# uln_0_02.net
KiCad netlist of a schematic drawn in EAGLE
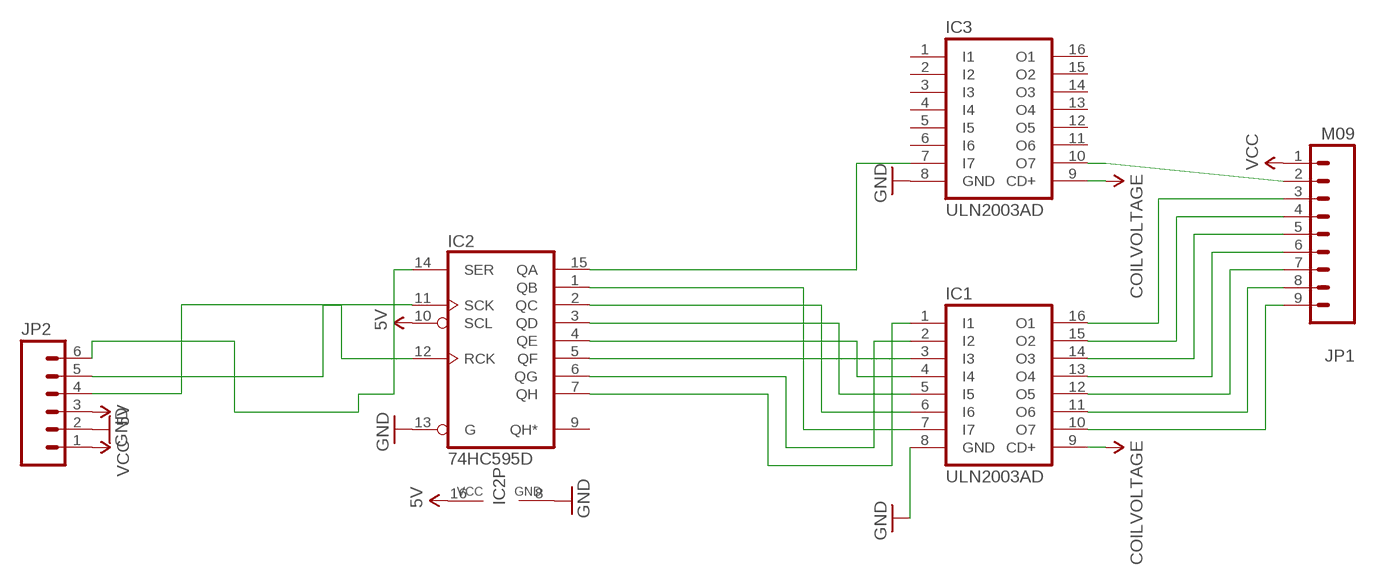
[diagram p0: schematic, sheet 1]

(export (version "E")
  (design (tool "Eeschema 10.0.6"))
  (components
    (comp (ref "IC1")
      (value "ULN2003AD")
      (footprint "eagle-import:SO16")
      (libsource (lib "eagle-import") (part "ULN2003AD"))
    )
    (comp (ref "IC2")
      (value "74HC595D")
      (footprint "eagle-import:SO16")
      (libsource (lib "eagle-import") (part "74595DHC"))
    )
    (comp (ref "IC3")
      (value "ULN2003AD")
      (footprint "eagle-import:SO16")
      (libsource (lib "eagle-import") (part "ULN2003AD"))
    )
    (comp (ref "JP1")
      (value "M09")
      (footprint "eagle-import:1X09")
      (libsource (lib "eagle-import") (part "M09"))
    )
    (comp (ref "JP2")
      (value "M06SIP")
      (footprint "eagle-import:1X06")
      (libsource (lib "eagle-import") (part "M06SIP"))
    )
  )
  (nets
    (net (code "1") (name "5V") (class "Default")
      (node (ref "IC2") (pin "10") (pinfunction "SCL_10") (pintype "input"))
      (node (ref "IC2") (pin "16") (pinfunction "VCC_16") (pintype "power_in"))
      (node (ref "JP2") (pin "3") (pinfunction "3_3") (pintype "passive"))
    )
    (net (code "2") (name "COILVOLTAGE") (class "Default")
      (node (ref "IC1") (pin "9") (pinfunction "CD+_9") (pintype "passive"))
      (node (ref "IC3") (pin "9") (pinfunction "CD+_9") (pintype "passive"))
      (node (ref "JP1") (pin "1") (pinfunction "1_1") (pintype "passive"))
      (node (ref "JP2") (pin "1") (pinfunction "1_1") (pintype "passive"))
    )
    (net (code "3") (name "GND") (class "Default")
      (node (ref "IC1") (pin "8") (pinfunction "GND_8") (pintype "power_in"))
      (node (ref "IC2") (pin "13") (pinfunction "G_13") (pintype "input"))
      (node (ref "IC2") (pin "8") (pinfunction "GND_8") (pintype "power_in"))
      (node (ref "IC3") (pin "8") (pinfunction "GND_8") (pintype "power_in"))
      (node (ref "JP2") (pin "2") (pinfunction "2_2") (pintype "passive"))
    )
    (net (code "4") (name "Net-(IC1-I1)") (class "Default")
      (node (ref "IC1") (pin "1") (pinfunction "I1_1") (pintype "input"))
      (node (ref "IC2") (pin "7") (pinfunction "QH_7") (pintype "tri_state"))
    )
    (net (code "5") (name "Net-(IC1-I2)") (class "Default")
      (node (ref "IC1") (pin "2") (pinfunction "I2_2") (pintype "input"))
      (node (ref "IC2") (pin "6") (pinfunction "QG_6") (pintype "tri_state"))
    )
    (net (code "6") (name "Net-(IC1-I3)") (class "Default")
      (node (ref "IC1") (pin "3") (pinfunction "I3_3") (pintype "input"))
      (node (ref "IC2") (pin "5") (pinfunction "QF_5") (pintype "tri_state"))
    )
    (net (code "7") (name "Net-(IC1-I4)") (class "Default")
      (node (ref "IC1") (pin "4") (pinfunction "I4_4") (pintype "input"))
      (node (ref "IC2") (pin "4") (pinfunction "QE_4") (pintype "tri_state"))
    )
    (net (code "8") (name "Net-(IC1-I5)") (class "Default")
      (node (ref "IC1") (pin "5") (pinfunction "I5_5") (pintype "input"))
      (node (ref "IC2") (pin "3") (pinfunction "QD_3") (pintype "tri_state"))
    )
    (net (code "9") (name "Net-(IC1-I6)") (class "Default")
      (node (ref "IC1") (pin "6") (pinfunction "I6_6") (pintype "input"))
      (node (ref "IC2") (pin "2") (pinfunction "QC_2") (pintype "tri_state"))
    )
    (net (code "10") (name "Net-(IC1-I7)") (class "Default")
      (node (ref "IC1") (pin "7") (pinfunction "I7_7") (pintype "input"))
      (node (ref "IC2") (pin "1") (pinfunction "QB_1") (pintype "tri_state"))
    )
    (net (code "11") (name "Net-(IC1-O1)") (class "Default")
      (node (ref "IC1") (pin "16") (pinfunction "O1_16") (pintype "open_collector"))
      (node (ref "JP1") (pin "3") (pinfunction "3_3") (pintype "passive"))
    )
    (net (code "12") (name "Net-(IC1-O2)") (class "Default")
      (node (ref "IC1") (pin "15") (pinfunction "O2_15") (pintype "open_collector"))
      (node (ref "JP1") (pin "4") (pinfunction "4_4") (pintype "passive"))
    )
    (net (code "13") (name "Net-(IC1-O3)") (class "Default")
      (node (ref "IC1") (pin "14") (pinfunction "O3_14") (pintype "open_collector"))
      (node (ref "JP1") (pin "5") (pinfunction "5_5") (pintype "passive"))
    )
    (net (code "14") (name "Net-(IC1-O4)") (class "Default")
      (node (ref "IC1") (pin "13") (pinfunction "O4_13") (pintype "open_collector"))
      (node (ref "JP1") (pin "6") (pinfunction "6_6") (pintype "passive"))
    )
    (net (code "15") (name "Net-(IC1-O5)") (class "Default")
      (node (ref "IC1") (pin "12") (pinfunction "O5_12") (pintype "open_collector"))
      (node (ref "JP1") (pin "7") (pinfunction "7_7") (pintype "passive"))
    )
    (net (code "16") (name "Net-(IC1-O6)") (class "Default")
      (node (ref "IC1") (pin "11") (pinfunction "O6_11") (pintype "open_collector"))
      (node (ref "JP1") (pin "8") (pinfunction "8_8") (pintype "passive"))
    )
    (net (code "17") (name "Net-(IC1-O7)") (class "Default")
      (node (ref "IC1") (pin "10") (pinfunction "O7_10") (pintype "open_collector"))
      (node (ref "JP1") (pin "9") (pinfunction "9_9") (pintype "passive"))
    )
    (net (code "18") (name "Net-(IC2A-QA)") (class "Default")
      (node (ref "IC2") (pin "15") (pinfunction "QA_15") (pintype "tri_state"))
      (node (ref "IC3") (pin "7") (pinfunction "I7_7") (pintype "input"))
    )
    (net (code "19") (name "Net-(IC2A-RCK)") (class "Default")
      (node (ref "IC2") (pin "12") (pinfunction "RCK_12") (pintype "input"))
      (node (ref "JP2") (pin "5") (pinfunction "5_5") (pintype "passive"))
    )
    (net (code "20") (name "Net-(IC2A-SCK)") (class "Default")
      (node (ref "IC2") (pin "11") (pinfunction "SCK_11") (pintype "input"))
      (node (ref "JP2") (pin "4") (pinfunction "4_4") (pintype "passive"))
    )
    (net (code "21") (name "Net-(IC2A-SER)") (class "Default")
      (node (ref "IC2") (pin "14") (pinfunction "SER_14") (pintype "input"))
      (node (ref "JP2") (pin "6") (pinfunction "6_6") (pintype "passive"))
    )
    (net (code "22") (name "Net-(IC3-O7)") (class "Default")
      (node (ref "IC3") (pin "10") (pinfunction "O7_10") (pintype "open_collector"))
      (node (ref "JP1") (pin "2") (pinfunction "2_2") (pintype "passive"))
    )
    (net (code "23") (name "unconnected-(IC2A-QH*-Pad9)") (class "Default")
      (node (ref "IC2") (pin "9") (pinfunction "QH*_9") (pintype "tri_state"))
    )
    (net (code "24") (name "unconnected-(IC3-I1-Pad1)") (class "Default")
      (node (ref "IC3") (pin "1") (pinfunction "I1_1") (pintype "input"))
    )
    (net (code "25") (name "unconnected-(IC3-I2-Pad2)") (class "Default")
      (node (ref "IC3") (pin "2") (pinfunction "I2_2") (pintype "input"))
    )
    (net (code "26") (name "unconnected-(IC3-I3-Pad3)") (class "Default")
      (node (ref "IC3") (pin "3") (pinfunction "I3_3") (pintype "input"))
    )
    (net (code "27") (name "unconnected-(IC3-I4-Pad4)") (class "Default")
      (node (ref "IC3") (pin "4") (pinfunction "I4_4") (pintype "input"))
    )
    (net (code "28") (name "unconnected-(IC3-I5-Pad5)") (class "Default")
      (node (ref "IC3") (pin "5") (pinfunction "I5_5") (pintype "input"))
    )
    (net (code "29") (name "unconnected-(IC3-I6-Pad6)") (class "Default")
      (node (ref "IC3") (pin "6") (pinfunction "I6_6") (pintype "input"))
    )
    (net (code "30") (name "unconnected-(IC3-O1-Pad16)") (class "Default")
      (node (ref "IC3") (pin "16") (pinfunction "O1_16") (pintype "open_collector"))
    )
    (net (code "31") (name "unconnected-(IC3-O2-Pad15)") (class "Default")
      (node (ref "IC3") (pin "15") (pinfunction "O2_15") (pintype "open_collector"))
    )
    (net (code "32") (name "unconnected-(IC3-O3-Pad14)") (class "Default")
      (node (ref "IC3") (pin "14") (pinfunction "O3_14") (pintype "open_collector"))
    )
    (net (code "33") (name "unconnected-(IC3-O4-Pad13)") (class "Default")
      (node (ref "IC3") (pin "13") (pinfunction "O4_13") (pintype "open_collector"))
    )
    (net (code "34") (name "unconnected-(IC3-O5-Pad12)") (class "Default")
      (node (ref "IC3") (pin "12") (pinfunction "O5_12") (pintype "open_collector"))
    )
    (net (code "35") (name "unconnected-(IC3-O6-Pad11)") (class "Default")
      (node (ref "IC3") (pin "11") (pinfunction "O6_11") (pintype "open_collector"))
    )
  )
)
